# MicroSD.net
KiCad netlist of a schematic drawn in Altium Designer
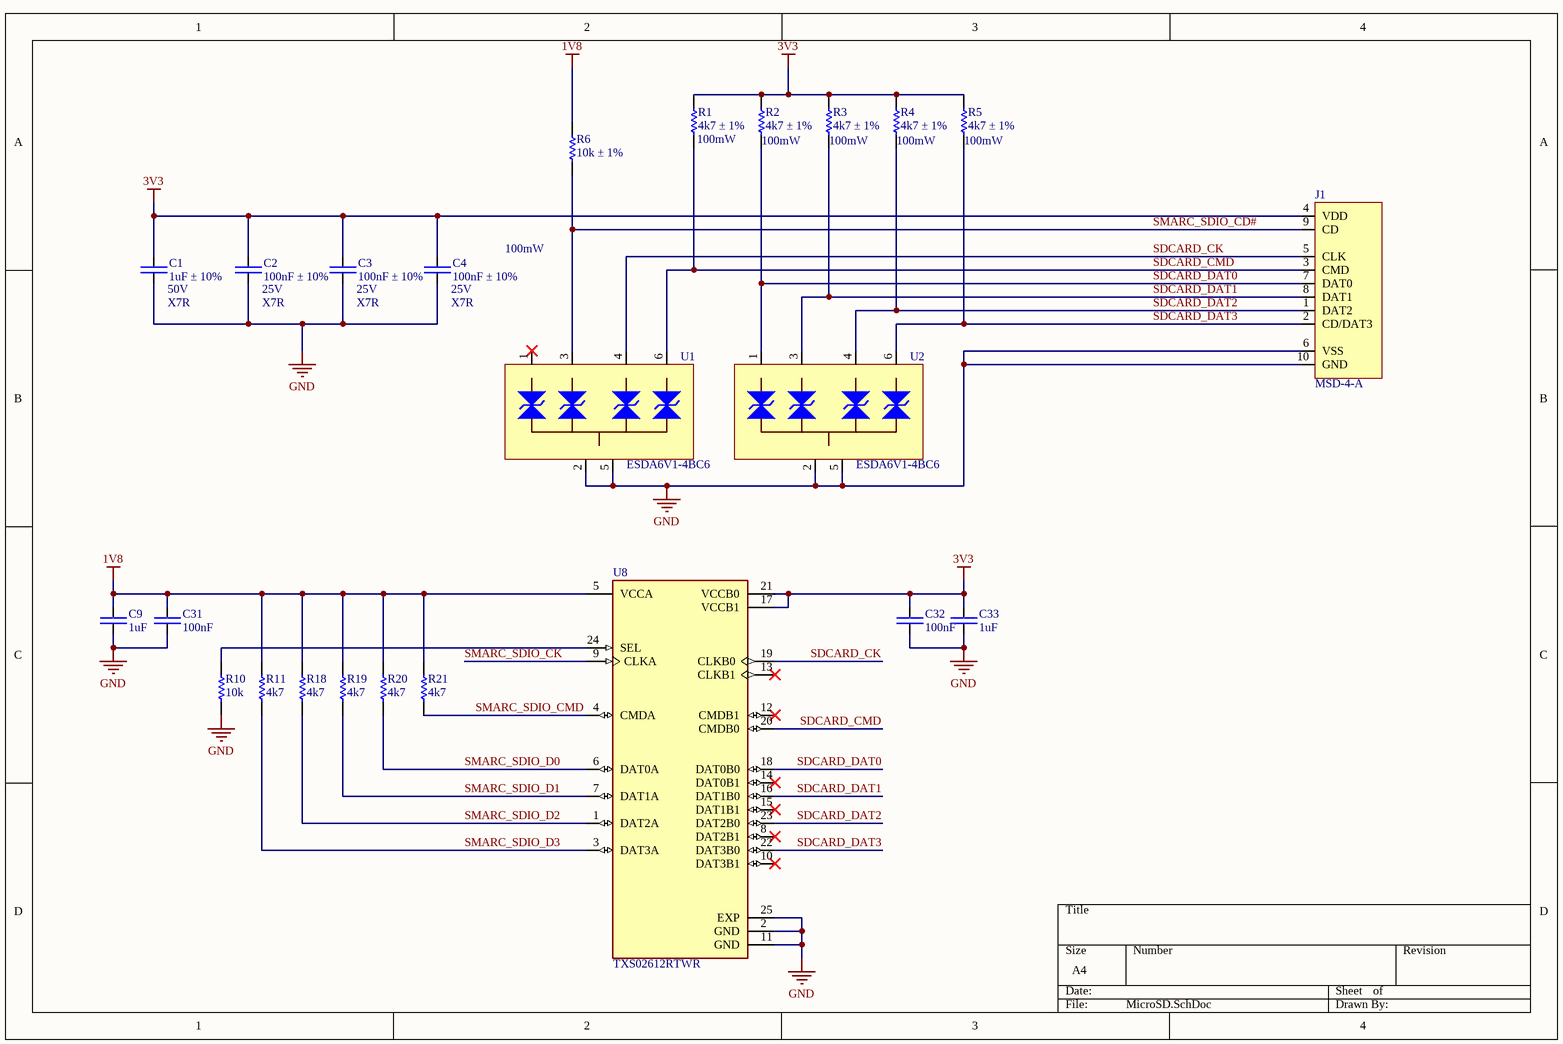
[diagram p0: MicroSD.SchDoc]

(export (version "E")
  (design (tool "Eeschema 10.0.6"))
  (components
    (comp (ref "C1")
      (value "1uF ± 10%")
      (footprint "CAP-0805")
      (description "Capacitor chip unpolarized. 0805")
      (libsource (lib "Master") (part "CAP-0805"))
    )
    (comp (ref "C2")
      (value "100nF ± 10%")
      (footprint "CAP-0603")
      (description "Capacitor chip unpolarized. 0603")
      (libsource (lib "Master") (part "CAP-0603"))
    )
    (comp (ref "C3")
      (value "100nF ± 10%")
      (footprint "CAP-0603")
      (description "Capacitor chip unpolarized. 0603")
      (libsource (lib "Master") (part "CAP-0603"))
    )
    (comp (ref "C4")
      (value "100nF ± 10%")
      (footprint "CAP-0603")
      (description "Capacitor chip unpolarized. 0603")
      (libsource (lib "Master") (part "CAP-0603"))
    )
    (comp (ref "C9")
      (value "1uF")
      (footprint "CAP-0805")
      (description "Capacitor chip unpolarized. 0805")
      (libsource (lib "Master") (part "CAP-0805"))
    )
    (comp (ref "C31")
      (value "100nF")
      (footprint "CAP-0603")
      (description "Capacitor chip unpolarized. 0603")
      (libsource (lib "Master") (part "CAP-0603"))
    )
    (comp (ref "C32")
      (value "100nF")
      (footprint "CAP-0603")
      (description "Capacitor chip unpolarized. 0603")
      (libsource (lib "Master") (part "CAP-0603"))
    )
    (comp (ref "C33")
      (value "1uF")
      (footprint "CAP-0805")
      (description "Capacitor chip unpolarized. 0805")
      (libsource (lib "Master") (part "CAP-0805"))
    )
    (comp (ref "J1")
      (value "MSD-4-A")
      (footprint "MSD-4-A")
      (description "Micro SD Connector")
      (libsource (lib "Master") (part "MSD-4-A"))
    )
    (comp (ref "R1")
      (value "4k7 ± 1%")
      (footprint "RES-0603")
      (description "Resistor chip. 0603")
      (libsource (lib "Master") (part "RES-0603"))
    )
    (comp (ref "R2")
      (value "4k7 ± 1%")
      (footprint "RES-0603")
      (description "Resistor chip. 0603")
      (libsource (lib "Master") (part "RES-0603"))
    )
    (comp (ref "R3")
      (value "4k7 ± 1%")
      (footprint "RES-0603")
      (description "Resistor chip. 0603")
      (libsource (lib "Master") (part "RES-0603"))
    )
    (comp (ref "R4")
      (value "4k7 ± 1%")
      (footprint "RES-0603")
      (description "Resistor chip. 0603")
      (libsource (lib "Master") (part "RES-0603"))
    )
    (comp (ref "R5")
      (value "4k7 ± 1%")
      (footprint "RES-0603")
      (description "Resistor chip. 0603")
      (libsource (lib "Master") (part "RES-0603"))
    )
    (comp (ref "R6")
      (value "10k ± 1%")
      (footprint "RES-0603")
      (description "Resistor chip. 0603")
      (libsource (lib "Master") (part "RES-0603"))
    )
    (comp (ref "R10")
      (value "10k")
      (footprint "RES-0603")
      (description "Resistor chip. 0603")
      (libsource (lib "Master") (part "RES-0603"))
    )
    (comp (ref "R11")
      (value "4k7")
      (footprint "RES-0603")
      (description "Resistor chip. 0603")
      (libsource (lib "Master") (part "RES-0603"))
    )
    (comp (ref "R18")
      (value "4k7")
      (footprint "RES-0603")
      (description "Resistor chip. 0603")
      (libsource (lib "Master") (part "RES-0603"))
    )
    (comp (ref "R19")
      (value "4k7")
      (footprint "RES-0603")
      (description "Resistor chip. 0603")
      (libsource (lib "Master") (part "RES-0603"))
    )
    (comp (ref "R20")
      (value "4k7")
      (footprint "RES-0603")
      (description "Resistor chip. 0603")
      (libsource (lib "Master") (part "RES-0603"))
    )
    (comp (ref "R21")
      (value "4k7")
      (footprint "RES-0603")
      (description "Resistor chip. 0603")
      (libsource (lib "Master") (part "RES-0603"))
    )
    (comp (ref "U1")
      (value "ESDA6V1-4BC6")
      (footprint "ESDA6V1-4BC6")
      (description "TVS Diode array 5VRM 7.4VC")
      (libsource (lib "Master") (part "ESDA6V1-4BC6"))
    )
    (comp (ref "U2")
      (value "ESDA6V1-4BC6")
      (footprint "ESDA6V1-4BC6")
      (description "TVS Diode array 5VRM 7.4VC")
      (libsource (lib "Master") (part "ESDA6V1-4BC6"))
    )
    (comp (ref "U8")
      (value "TXS02612RTWR")
      (footprint "TXS02612RTWR")
      (description "Voltage Level Translator 24-Pin WQFN EP T/R")
      (fields (field (name "MF") "Texas Instruments") (field (name "MP") "TXS02612RTWR ."))
      (libsource (lib "Master") (part "TXS02612RTWR"))
    )
  )
  (nets
    (net (code "1") (name "/SDCARD_CK") (class "Default")
      (node (ref "J1") (pin "5") (pinfunction "CLK_5") (pintype "passive"))
      (node (ref "U1") (pin "4") (pintype "passive"))
      (node (ref "U8") (pin "19") (pinfunction "CLKB0_19") (pintype "output"))
    )
    (net (code "2") (name "/SDCARD_CMD") (class "Default")
      (node (ref "J1") (pin "3") (pinfunction "CMD_3") (pintype "passive"))
      (node (ref "R1") (pin "1") (pintype "passive"))
      (node (ref "U1") (pin "6") (pintype "passive"))
      (node (ref "U8") (pin "20") (pinfunction "CMDB0_20") (pintype "bidirectional"))
    )
    (net (code "3") (name "/SDCARD_DAT0") (class "Default")
      (node (ref "J1") (pin "7") (pinfunction "DAT0_7") (pintype "passive"))
      (node (ref "R2") (pin "1") (pintype "passive"))
      (node (ref "U2") (pin "1") (pintype "passive"))
      (node (ref "U8") (pin "18") (pinfunction "DAT0B0_18") (pintype "bidirectional"))
    )
    (net (code "4") (name "/SDCARD_DAT1") (class "Default")
      (node (ref "J1") (pin "8") (pinfunction "DAT1_8") (pintype "passive"))
      (node (ref "R3") (pin "1") (pintype "passive"))
      (node (ref "U2") (pin "3") (pintype "passive"))
      (node (ref "U8") (pin "16") (pinfunction "DAT1B0_16") (pintype "bidirectional"))
    )
    (net (code "5") (name "/SDCARD_DAT2") (class "Default")
      (node (ref "J1") (pin "1") (pinfunction "DAT2_1") (pintype "passive"))
      (node (ref "R4") (pin "1") (pintype "passive"))
      (node (ref "U2") (pin "4") (pintype "passive"))
      (node (ref "U8") (pin "23") (pinfunction "DAT2B0_23") (pintype "bidirectional"))
    )
    (net (code "6") (name "/SDCARD_DAT3") (class "Default")
      (node (ref "J1") (pin "2") (pinfunction "CD/DAT3_2") (pintype "passive"))
      (node (ref "R5") (pin "1") (pintype "passive"))
      (node (ref "U2") (pin "6") (pintype "passive"))
      (node (ref "U8") (pin "22") (pinfunction "DAT3B0_22") (pintype "bidirectional"))
    )
    (net (code "7") (name "/SMARC_SDIO_CD#") (class "Default")
      (node (ref "J1") (pin "9") (pinfunction "CD_9") (pintype "passive"))
      (node (ref "R6") (pin "1") (pintype "passive"))
      (node (ref "U1") (pin "3") (pintype "passive"))
    )
    (net (code "8") (name "/SMARC_SDIO_CK") (class "Default")
      (node (ref "U8") (pin "9") (pinfunction "CLKA_9") (pintype "input"))
    )
    (net (code "9") (name "/SMARC_SDIO_CMD") (class "Default")
      (node (ref "R21") (pin "1") (pintype "passive"))
      (node (ref "U8") (pin "4") (pinfunction "CMDA_4") (pintype "bidirectional"))
    )
    (net (code "10") (name "/SMARC_SDIO_D0") (class "Default")
      (node (ref "R20") (pin "1") (pintype "passive"))
      (node (ref "U8") (pin "6") (pinfunction "DAT0A_6") (pintype "bidirectional"))
    )
    (net (code "11") (name "/SMARC_SDIO_D1") (class "Default")
      (node (ref "R19") (pin "1") (pintype "passive"))
      (node (ref "U8") (pin "7") (pinfunction "DAT1A_7") (pintype "bidirectional"))
    )
    (net (code "12") (name "/SMARC_SDIO_D2") (class "Default")
      (node (ref "R18") (pin "1") (pintype "passive"))
      (node (ref "U8") (pin "1") (pinfunction "DAT2A_1") (pintype "bidirectional"))
    )
    (net (code "13") (name "/SMARC_SDIO_D3") (class "Default")
      (node (ref "R11") (pin "1") (pintype "passive"))
      (node (ref "U8") (pin "3") (pinfunction "DAT3A_3") (pintype "bidirectional"))
    )
    (net (code "14") (name "1V8") (class "Default")
      (node (ref "C31") (pin "2") (pintype "passive"))
      (node (ref "C9") (pin "2") (pintype "passive"))
      (node (ref "R11") (pin "2") (pintype "passive"))
      (node (ref "R18") (pin "2") (pintype "passive"))
      (node (ref "R19") (pin "2") (pintype "passive"))
      (node (ref "R20") (pin "2") (pintype "passive"))
      (node (ref "R21") (pin "2") (pintype "passive"))
      (node (ref "R6") (pin "2") (pintype "passive"))
      (node (ref "U8") (pin "5") (pinfunction "VCCA_5") (pintype "power_in"))
    )
    (net (code "15") (name "3V3") (class "Default")
      (node (ref "C1") (pin "2") (pintype "passive"))
      (node (ref "C2") (pin "2") (pintype "passive"))
      (node (ref "C3") (pin "2") (pintype "passive"))
      (node (ref "C32") (pin "2") (pintype "passive"))
      (node (ref "C33") (pin "2") (pintype "passive"))
      (node (ref "C4") (pin "2") (pintype "passive"))
      (node (ref "J1") (pin "4") (pinfunction "VDD_4") (pintype "passive"))
      (node (ref "R1") (pin "2") (pintype "passive"))
      (node (ref "R2") (pin "2") (pintype "passive"))
      (node (ref "R3") (pin "2") (pintype "passive"))
      (node (ref "R4") (pin "2") (pintype "passive"))
      (node (ref "R5") (pin "2") (pintype "passive"))
      (node (ref "U8") (pin "17") (pinfunction "VCCB1_17") (pintype "power_in"))
      (node (ref "U8") (pin "21") (pinfunction "VCCB0_21") (pintype "power_in"))
    )
    (net (code "16") (name "GND") (class "Default")
      (node (ref "C1") (pin "1") (pintype "passive"))
      (node (ref "C2") (pin "1") (pintype "passive"))
      (node (ref "C3") (pin "1") (pintype "passive"))
      (node (ref "C31") (pin "1") (pintype "passive"))
      (node (ref "C32") (pin "1") (pintype "passive"))
      (node (ref "C33") (pin "1") (pintype "passive"))
      (node (ref "C4") (pin "1") (pintype "passive"))
      (node (ref "C9") (pin "1") (pintype "passive"))
      (node (ref "J1") (pin "10") (pinfunction "GND_10") (pintype "passive"))
      (node (ref "J1") (pin "6") (pinfunction "VSS_6") (pintype "passive"))
      (node (ref "R10") (pin "1") (pintype "passive"))
      (node (ref "U1") (pin "2") (pintype "passive"))
      (node (ref "U1") (pin "5") (pintype "passive"))
      (node (ref "U2") (pin "2") (pintype "passive"))
      (node (ref "U2") (pin "5") (pintype "passive"))
      (node (ref "U8") (pin "11") (pinfunction "GND_11") (pintype "power_in"))
      (node (ref "U8") (pin "2") (pinfunction "GND_2") (pintype "power_in"))
      (node (ref "U8") (pin "25") (pinfunction "EXP_25") (pintype "passive"))
    )
    (net (code "17") (name "Net-(U8-SEL)") (class "Default")
      (node (ref "R10") (pin "2") (pintype "passive"))
      (node (ref "U8") (pin "24") (pinfunction "SEL_24") (pintype "input"))
    )
    (net (code "18") (name "unconnected-(U1-Pad1)") (class "Default")
      (node (ref "U1") (pin "1") (pintype "passive+no_connect"))
    )
    (net (code "19") (name "unconnected-(U8-CLKB1-Pad13)") (class "Default")
      (node (ref "U8") (pin "13") (pinfunction "CLKB1_13") (pintype "output+no_connect"))
    )
    (net (code "20") (name "unconnected-(U8-CMDB1-Pad12)") (class "Default")
      (node (ref "U8") (pin "12") (pinfunction "CMDB1_12") (pintype "bidirectional+no_connect"))
    )
    (net (code "21") (name "unconnected-(U8-DAT0B1-Pad14)") (class "Default")
      (node (ref "U8") (pin "14") (pinfunction "DAT0B1_14") (pintype "bidirectional+no_connect"))
    )
    (net (code "22") (name "unconnected-(U8-DAT1B1-Pad15)") (class "Default")
      (node (ref "U8") (pin "15") (pinfunction "DAT1B1_15") (pintype "bidirectional+no_connect"))
    )
    (net (code "23") (name "unconnected-(U8-DAT2B1-Pad8)") (class "Default")
      (node (ref "U8") (pin "8") (pinfunction "DAT2B1_8") (pintype "bidirectional+no_connect"))
    )
    (net (code "24") (name "unconnected-(U8-DAT3B1-Pad10)") (class "Default")
      (node (ref "U8") (pin "10") (pinfunction "DAT3B1_10") (pintype "bidirectional+no_connect"))
    )
  )
)
